# schema1.net
KiCad netlist of a schematic drawn in Altium Designer
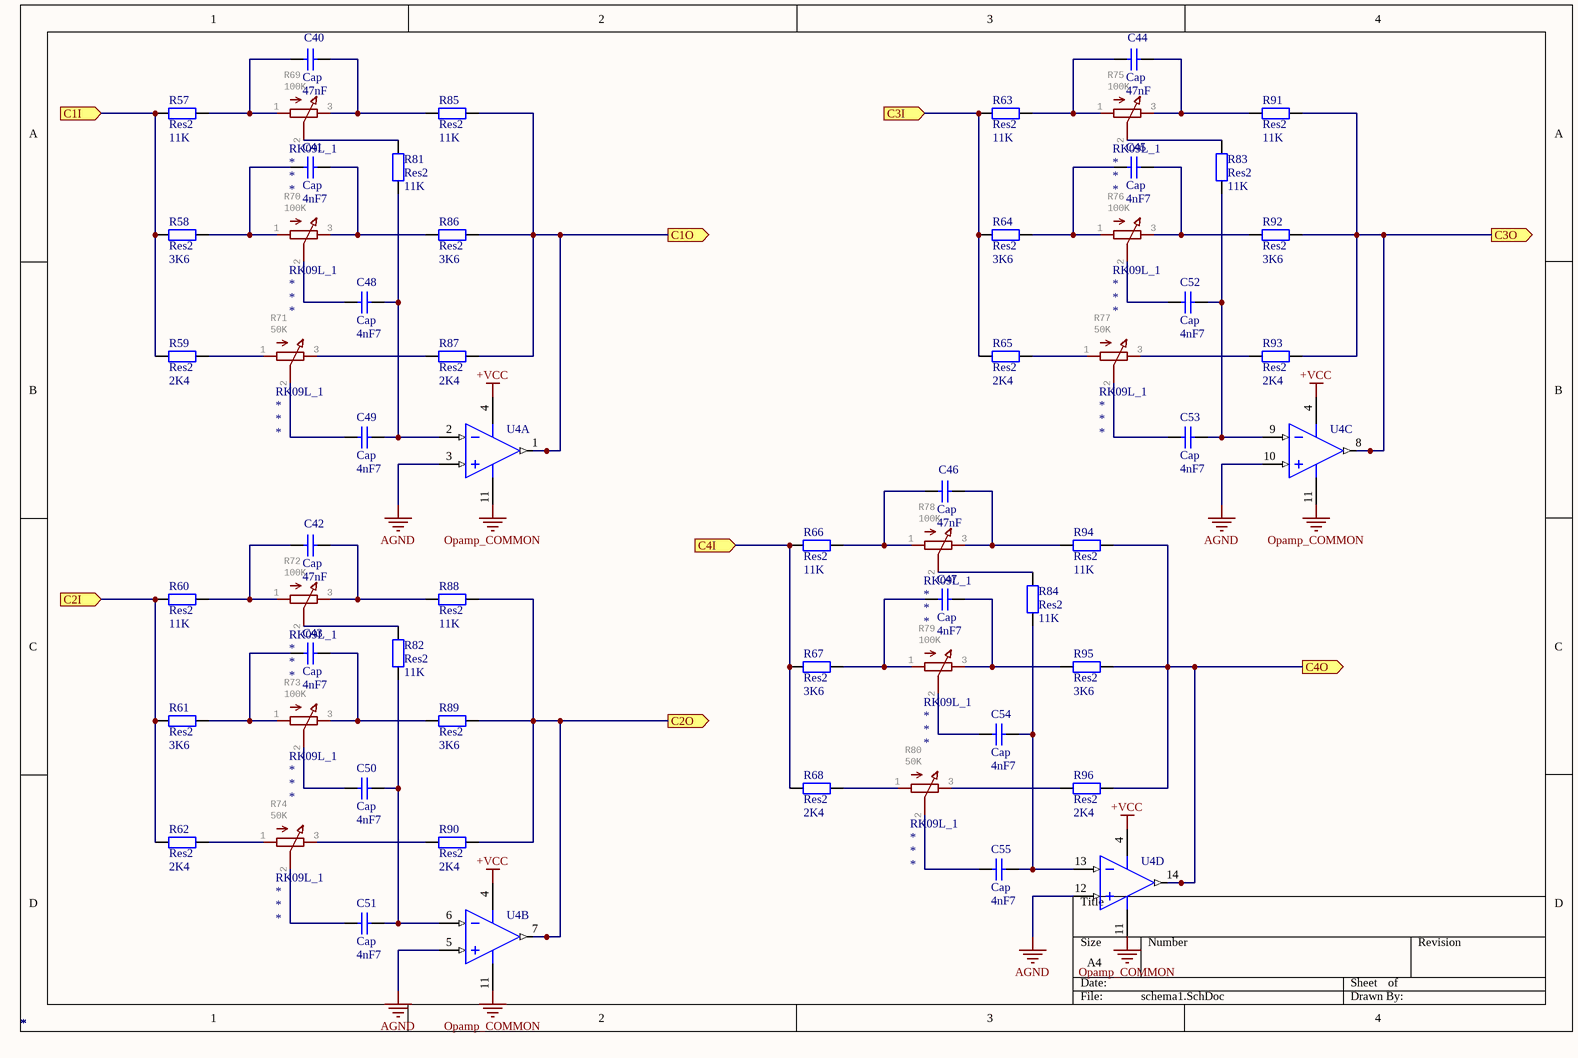
[diagram p0: schema1.SchDoc]

(export (version "E")
  (design (tool "Eeschema 10.0.6"))
  (components
    (comp (ref "C40")
      (value "Cap")
      (footprint "SMD_CAPACITOR")
      (description "Capacitor")
      (fields (field (name "ALTIUM_VALUE") "47nF") (field (name "PUBLISHER") "Altium Limited"))
      (libsource (lib "Miscellaneous Devices") (part "Cap"))
    )
    (comp (ref "C41")
      (value "Cap")
      (footprint "SMD_CAPACITOR")
      (description "Capacitor")
      (fields (field (name "ALTIUM_VALUE") "4nF7") (field (name "PUBLISHER") "Altium Limited"))
      (libsource (lib "Miscellaneous Devices") (part "Cap"))
    )
    (comp (ref "C42")
      (value "Cap")
      (footprint "SMD_CAPACITOR")
      (description "Capacitor")
      (fields (field (name "ALTIUM_VALUE") "47nF") (field (name "PUBLISHER") "Altium Limited"))
      (libsource (lib "Miscellaneous Devices") (part "Cap"))
    )
    (comp (ref "C43")
      (value "Cap")
      (footprint "SMD_CAPACITOR")
      (description "Capacitor")
      (fields (field (name "ALTIUM_VALUE") "4nF7") (field (name "PUBLISHER") "Altium Limited"))
      (libsource (lib "Miscellaneous Devices") (part "Cap"))
    )
    (comp (ref "C44")
      (value "Cap")
      (footprint "SMD_CAPACITOR")
      (description "Capacitor")
      (fields (field (name "ALTIUM_VALUE") "47nF") (field (name "PUBLISHER") "Altium Limited"))
      (libsource (lib "Miscellaneous Devices") (part "Cap"))
    )
    (comp (ref "C45")
      (value "Cap")
      (footprint "SMD_CAPACITOR")
      (description "Capacitor")
      (fields (field (name "ALTIUM_VALUE") "4nF7") (field (name "PUBLISHER") "Altium Limited"))
      (libsource (lib "Miscellaneous Devices") (part "Cap"))
    )
    (comp (ref "C46")
      (value "Cap")
      (footprint "SMD_CAPACITOR")
      (description "Capacitor")
      (fields (field (name "ALTIUM_VALUE") "47nF") (field (name "PUBLISHER") "Altium Limited"))
      (libsource (lib "Miscellaneous Devices") (part "Cap"))
    )
    (comp (ref "C47")
      (value "Cap")
      (footprint "SMD_CAPACITOR")
      (description "Capacitor")
      (fields (field (name "ALTIUM_VALUE") "4nF7") (field (name "PUBLISHER") "Altium Limited"))
      (libsource (lib "Miscellaneous Devices") (part "Cap"))
    )
    (comp (ref "C48")
      (value "Cap")
      (footprint "SMD_CAPACITOR")
      (description "Capacitor")
      (fields (field (name "ALTIUM_VALUE") "4nF7") (field (name "PUBLISHER") "Altium Limited"))
      (libsource (lib "Miscellaneous Devices") (part "Cap"))
    )
    (comp (ref "C49")
      (value "Cap")
      (footprint "SMD_CAPACITOR")
      (description "Capacitor")
      (fields (field (name "ALTIUM_VALUE") "4nF7") (field (name "PUBLISHER") "Altium Limited"))
      (libsource (lib "Miscellaneous Devices") (part "Cap"))
    )
    (comp (ref "C50")
      (value "Cap")
      (footprint "SMD_CAPACITOR")
      (description "Capacitor")
      (fields (field (name "ALTIUM_VALUE") "4nF7") (field (name "PUBLISHER") "Altium Limited"))
      (libsource (lib "Miscellaneous Devices") (part "Cap"))
    )
    (comp (ref "C51")
      (value "Cap")
      (footprint "SMD_CAPACITOR")
      (description "Capacitor")
      (fields (field (name "ALTIUM_VALUE") "4nF7") (field (name "PUBLISHER") "Altium Limited"))
      (libsource (lib "Miscellaneous Devices") (part "Cap"))
    )
    (comp (ref "C52")
      (value "Cap")
      (footprint "SMD_CAPACITOR")
      (description "Capacitor")
      (fields (field (name "ALTIUM_VALUE") "4nF7") (field (name "PUBLISHER") "Altium Limited"))
      (libsource (lib "Miscellaneous Devices") (part "Cap"))
    )
    (comp (ref "C53")
      (value "Cap")
      (footprint "SMD_CAPACITOR")
      (description "Capacitor")
      (fields (field (name "ALTIUM_VALUE") "4nF7") (field (name "PUBLISHER") "Altium Limited"))
      (libsource (lib "Miscellaneous Devices") (part "Cap"))
    )
    (comp (ref "C54")
      (value "Cap")
      (footprint "SMD_CAPACITOR")
      (description "Capacitor")
      (fields (field (name "ALTIUM_VALUE") "4nF7") (field (name "PUBLISHER") "Altium Limited"))
      (libsource (lib "Miscellaneous Devices") (part "Cap"))
    )
    (comp (ref "C55")
      (value "Cap")
      (footprint "SMD_CAPACITOR")
      (description "Capacitor")
      (fields (field (name "ALTIUM_VALUE") "4nF7") (field (name "PUBLISHER") "Altium Limited"))
      (libsource (lib "Miscellaneous Devices") (part "Cap"))
    )
    (comp (ref "R57")
      (value "Res2")
      (footprint "SMD_RESISTOR")
      (description "Resistor")
      (fields (field (name "ALTIUM_VALUE") "11K") (field (name "PUBLISHER") "Altium Limited"))
      (libsource (lib "Miscellaneous Devices") (part "Res2"))
    )
    (comp (ref "R58")
      (value "Res2")
      (footprint "SMD_RESISTOR")
      (description "Resistor")
      (fields (field (name "ALTIUM_VALUE") "3K6") (field (name "PUBLISHER") "Altium Limited"))
      (libsource (lib "Miscellaneous Devices") (part "Res2"))
    )
    (comp (ref "R59")
      (value "Res2")
      (footprint "SMD_RESISTOR")
      (description "Resistor")
      (fields (field (name "ALTIUM_VALUE") "2K4") (field (name "PUBLISHER") "Altium Limited"))
      (libsource (lib "Miscellaneous Devices") (part "Res2"))
    )
    (comp (ref "R60")
      (value "Res2")
      (footprint "SMD_RESISTOR")
      (description "Resistor")
      (fields (field (name "ALTIUM_VALUE") "11K") (field (name "PUBLISHER") "Altium Limited"))
      (libsource (lib "Miscellaneous Devices") (part "Res2"))
    )
    (comp (ref "R61")
      (value "Res2")
      (footprint "SMD_RESISTOR")
      (description "Resistor")
      (fields (field (name "ALTIUM_VALUE") "3K6") (field (name "PUBLISHER") "Altium Limited"))
      (libsource (lib "Miscellaneous Devices") (part "Res2"))
    )
    (comp (ref "R62")
      (value "Res2")
      (footprint "SMD_RESISTOR")
      (description "Resistor")
      (fields (field (name "ALTIUM_VALUE") "2K4") (field (name "PUBLISHER") "Altium Limited"))
      (libsource (lib "Miscellaneous Devices") (part "Res2"))
    )
    (comp (ref "R63")
      (value "Res2")
      (footprint "SMD_RESISTOR")
      (description "Resistor")
      (fields (field (name "ALTIUM_VALUE") "11K") (field (name "PUBLISHER") "Altium Limited"))
      (libsource (lib "Miscellaneous Devices") (part "Res2"))
    )
    (comp (ref "R64")
      (value "Res2")
      (footprint "SMD_RESISTOR")
      (description "Resistor")
      (fields (field (name "ALTIUM_VALUE") "3K6") (field (name "PUBLISHER") "Altium Limited"))
      (libsource (lib "Miscellaneous Devices") (part "Res2"))
    )
    (comp (ref "R65")
      (value "Res2")
      (footprint "SMD_RESISTOR")
      (description "Resistor")
      (fields (field (name "ALTIUM_VALUE") "2K4") (field (name "PUBLISHER") "Altium Limited"))
      (libsource (lib "Miscellaneous Devices") (part "Res2"))
    )
    (comp (ref "R66")
      (value "Res2")
      (footprint "SMD_RESISTOR")
      (description "Resistor")
      (fields (field (name "ALTIUM_VALUE") "11K") (field (name "PUBLISHER") "Altium Limited"))
      (libsource (lib "Miscellaneous Devices") (part "Res2"))
    )
    (comp (ref "R67")
      (value "Res2")
      (footprint "SMD_RESISTOR")
      (description "Resistor")
      (fields (field (name "ALTIUM_VALUE") "3K6") (field (name "PUBLISHER") "Altium Limited"))
      (libsource (lib "Miscellaneous Devices") (part "Res2"))
    )
    (comp (ref "R68")
      (value "Res2")
      (footprint "SMD_RESISTOR")
      (description "Resistor")
      (fields (field (name "ALTIUM_VALUE") "2K4") (field (name "PUBLISHER") "Altium Limited"))
      (libsource (lib "Miscellaneous Devices") (part "Res2"))
    )
    (comp (ref "R69")
      (value "100K")
      (footprint "RK09L1140A65")
      (fields
        (field (name "ALTIUM_UNNAMED_1") "*")
        (field (name "ALTIUM_UNNAMED_2") "*")
        (field (name "ALTIUM_UNNAMED_3") "*")
        (field (name "ALTIUM_UNNAMED_4") "RK09L_1")
        (field (name "ALTIUM_UNNAMED_5") "*")
        (field (name "ALTIUM_UNNAMED_6") "*")
        (field (name "ALTIUM_UNNAMED_7") "*")
        (field (name "ALTIUM_UNNAMED_8") "*")
        (field (name "ALTIUM_UNNAMED_9") "*")
        (field (name "LIBRARYNAME") "SD_Pots")
      )
      (libsource (lib "equalizer_project") (part "RK09L_1"))
    )
    (comp (ref "R70")
      (value "100K")
      (footprint "RK09L1140A65")
      (fields
        (field (name "ALTIUM_UNNAMED_1") "*")
        (field (name "ALTIUM_UNNAMED_2") "*")
        (field (name "ALTIUM_UNNAMED_3") "*")
        (field (name "ALTIUM_UNNAMED_4") "RK09L_1")
        (field (name "ALTIUM_UNNAMED_5") "*")
        (field (name "ALTIUM_UNNAMED_6") "*")
        (field (name "ALTIUM_UNNAMED_7") "*")
        (field (name "ALTIUM_UNNAMED_8") "*")
        (field (name "ALTIUM_UNNAMED_9") "*")
        (field (name "LIBRARYNAME") "SD_Pots")
      )
      (libsource (lib "equalizer_project") (part "RK09L_1"))
    )
    (comp (ref "R71")
      (value "50K")
      (footprint "RK09L1140A65")
      (fields
        (field (name "ALTIUM_UNNAMED_1") "*")
        (field (name "ALTIUM_UNNAMED_2") "*")
        (field (name "ALTIUM_UNNAMED_3") "*")
        (field (name "ALTIUM_UNNAMED_4") "RK09L_1")
        (field (name "ALTIUM_UNNAMED_5") "*")
        (field (name "ALTIUM_UNNAMED_6") "*")
        (field (name "ALTIUM_UNNAMED_7") "*")
        (field (name "ALTIUM_UNNAMED_8") "*")
        (field (name "ALTIUM_UNNAMED_9") "*")
        (field (name "LIBRARYNAME") "SD_Pots")
      )
      (libsource (lib "equalizer_project") (part "RK09L_1"))
    )
    (comp (ref "R72")
      (value "100K")
      (footprint "RK09L1140A65")
      (fields
        (field (name "ALTIUM_UNNAMED_1") "*")
        (field (name "ALTIUM_UNNAMED_2") "*")
        (field (name "ALTIUM_UNNAMED_3") "*")
        (field (name "ALTIUM_UNNAMED_4") "RK09L_1")
        (field (name "ALTIUM_UNNAMED_5") "*")
        (field (name "ALTIUM_UNNAMED_6") "*")
        (field (name "ALTIUM_UNNAMED_7") "*")
        (field (name "ALTIUM_UNNAMED_8") "*")
        (field (name "ALTIUM_UNNAMED_9") "*")
        (field (name "LIBRARYNAME") "SD_Pots")
      )
      (libsource (lib "equalizer_project") (part "RK09L_1"))
    )
    (comp (ref "R73")
      (value "100K")
      (footprint "RK09L1140A65")
      (fields
        (field (name "ALTIUM_UNNAMED_1") "*")
        (field (name "ALTIUM_UNNAMED_2") "*")
        (field (name "ALTIUM_UNNAMED_3") "*")
        (field (name "ALTIUM_UNNAMED_4") "RK09L_1")
        (field (name "ALTIUM_UNNAMED_5") "*")
        (field (name "ALTIUM_UNNAMED_6") "*")
        (field (name "ALTIUM_UNNAMED_7") "*")
        (field (name "ALTIUM_UNNAMED_8") "*")
        (field (name "ALTIUM_UNNAMED_9") "*")
        (field (name "LIBRARYNAME") "SD_Pots")
      )
      (libsource (lib "equalizer_project") (part "RK09L_1"))
    )
    (comp (ref "R74")
      (value "50K")
      (footprint "RK09L1140A65")
      (fields
        (field (name "ALTIUM_UNNAMED_1") "*")
        (field (name "ALTIUM_UNNAMED_2") "*")
        (field (name "ALTIUM_UNNAMED_3") "*")
        (field (name "ALTIUM_UNNAMED_4") "RK09L_1")
        (field (name "ALTIUM_UNNAMED_5") "*")
        (field (name "ALTIUM_UNNAMED_6") "*")
        (field (name "ALTIUM_UNNAMED_7") "*")
        (field (name "ALTIUM_UNNAMED_8") "*")
        (field (name "ALTIUM_UNNAMED_9") "*")
        (field (name "LIBRARYNAME") "SD_Pots")
      )
      (libsource (lib "equalizer_project") (part "RK09L_1"))
    )
    (comp (ref "R75")
      (value "100K")
      (footprint "RK09L1140A65")
      (fields
        (field (name "ALTIUM_UNNAMED_1") "*")
        (field (name "ALTIUM_UNNAMED_2") "*")
        (field (name "ALTIUM_UNNAMED_3") "*")
        (field (name "ALTIUM_UNNAMED_4") "RK09L_1")
        (field (name "ALTIUM_UNNAMED_5") "*")
        (field (name "ALTIUM_UNNAMED_6") "*")
        (field (name "ALTIUM_UNNAMED_7") "*")
        (field (name "ALTIUM_UNNAMED_8") "*")
        (field (name "ALTIUM_UNNAMED_9") "*")
        (field (name "LIBRARYNAME") "SD_Pots")
      )
      (libsource (lib "equalizer_project") (part "RK09L_1"))
    )
    (comp (ref "R76")
      (value "100K")
      (footprint "RK09L1140A65")
      (fields
        (field (name "ALTIUM_UNNAMED_1") "*")
        (field (name "ALTIUM_UNNAMED_2") "*")
        (field (name "ALTIUM_UNNAMED_3") "*")
        (field (name "ALTIUM_UNNAMED_4") "RK09L_1")
        (field (name "ALTIUM_UNNAMED_5") "*")
        (field (name "ALTIUM_UNNAMED_6") "*")
        (field (name "ALTIUM_UNNAMED_7") "*")
        (field (name "ALTIUM_UNNAMED_8") "*")
        (field (name "ALTIUM_UNNAMED_9") "*")
        (field (name "LIBRARYNAME") "SD_Pots")
      )
      (libsource (lib "equalizer_project") (part "RK09L_1"))
    )
    (comp (ref "R77")
      (value "50K")
      (footprint "RK09L1140A65")
      (fields
        (field (name "ALTIUM_UNNAMED_1") "*")
        (field (name "ALTIUM_UNNAMED_2") "*")
        (field (name "ALTIUM_UNNAMED_3") "*")
        (field (name "ALTIUM_UNNAMED_4") "RK09L_1")
        (field (name "ALTIUM_UNNAMED_5") "*")
        (field (name "ALTIUM_UNNAMED_6") "*")
        (field (name "ALTIUM_UNNAMED_7") "*")
        (field (name "ALTIUM_UNNAMED_8") "*")
        (field (name "ALTIUM_UNNAMED_9") "*")
        (field (name "LIBRARYNAME") "SD_Pots")
      )
      (libsource (lib "equalizer_project") (part "RK09L_1"))
    )
    (comp (ref "R78")
      (value "100K")
      (footprint "RK09L1140A65")
      (fields
        (field (name "ALTIUM_UNNAMED_1") "*")
        (field (name "ALTIUM_UNNAMED_2") "*")
        (field (name "ALTIUM_UNNAMED_3") "*")
        (field (name "ALTIUM_UNNAMED_4") "RK09L_1")
        (field (name "ALTIUM_UNNAMED_5") "*")
        (field (name "ALTIUM_UNNAMED_6") "*")
        (field (name "ALTIUM_UNNAMED_7") "*")
        (field (name "ALTIUM_UNNAMED_8") "*")
        (field (name "ALTIUM_UNNAMED_9") "*")
        (field (name "LIBRARYNAME") "SD_Pots")
      )
      (libsource (lib "equalizer_project") (part "RK09L_1"))
    )
    (comp (ref "R79")
      (value "100K")
      (footprint "RK09L1140A65")
      (fields
        (field (name "ALTIUM_UNNAMED_1") "*")
        (field (name "ALTIUM_UNNAMED_2") "*")
        (field (name "ALTIUM_UNNAMED_3") "*")
        (field (name "ALTIUM_UNNAMED_4") "RK09L_1")
        (field (name "ALTIUM_UNNAMED_5") "*")
        (field (name "ALTIUM_UNNAMED_6") "*")
        (field (name "ALTIUM_UNNAMED_7") "*")
        (field (name "ALTIUM_UNNAMED_8") "*")
        (field (name "ALTIUM_UNNAMED_9") "*")
        (field (name "LIBRARYNAME") "SD_Pots")
      )
      (libsource (lib "equalizer_project") (part "RK09L_1"))
    )
    (comp (ref "R80")
      (value "50K")
      (footprint "RK09L1140A65")
      (fields
        (field (name "ALTIUM_UNNAMED_1") "*")
        (field (name "ALTIUM_UNNAMED_2") "*")
        (field (name "ALTIUM_UNNAMED_3") "*")
        (field (name "ALTIUM_UNNAMED_4") "RK09L_1")
        (field (name "ALTIUM_UNNAMED_5") "*")
        (field (name "ALTIUM_UNNAMED_6") "*")
        (field (name "ALTIUM_UNNAMED_7") "*")
        (field (name "ALTIUM_UNNAMED_8") "*")
        (field (name "ALTIUM_UNNAMED_9") "*")
        (field (name "LIBRARYNAME") "SD_Pots")
      )
      (libsource (lib "equalizer_project") (part "RK09L_1"))
    )
    (comp (ref "R81")
      (value "Res2")
      (footprint "SMD_RESISTOR")
      (description "Resistor")
      (fields (field (name "ALTIUM_VALUE") "11K") (field (name "PUBLISHER") "Altium Limited"))
      (libsource (lib "") (part "Res2_1"))
    )
    (comp (ref "R82")
      (value "Res2")
      (footprint "SMD_RESISTOR")
      (description "Resistor")
      (fields (field (name "ALTIUM_VALUE") "11K") (field (name "PUBLISHER") "Altium Limited"))
      (libsource (lib "") (part "Res2_1"))
    )
    (comp (ref "R83")
      (value "Res2")
      (footprint "SMD_RESISTOR")
      (description "Resistor")
      (fields (field (name "ALTIUM_VALUE") "11K") (field (name "PUBLISHER") "Altium Limited"))
      (libsource (lib "") (part "Res2_1"))
    )
    (comp (ref "R84")
      (value "Res2")
      (footprint "SMD_RESISTOR")
      (description "Resistor")
      (fields (field (name "ALTIUM_VALUE") "11K") (field (name "PUBLISHER") "Altium Limited"))
      (libsource (lib "") (part "Res2_1"))
    )
    (comp (ref "R85")
      (value "Res2")
      (footprint "SMD_RESISTOR")
      (description "Resistor")
      (fields (field (name "ALTIUM_VALUE") "11K") (field (name "PUBLISHER") "Altium Limited"))
      (libsource (lib "Miscellaneous Devices") (part "Res2"))
    )
    (comp (ref "R86")
      (value "Res2")
      (footprint "SMD_RESISTOR")
      (description "Resistor")
      (fields (field (name "ALTIUM_VALUE") "3K6") (field (name "PUBLISHER") "Altium Limited"))
      (libsource (lib "Miscellaneous Devices") (part "Res2"))
    )
    (comp (ref "R87")
      (value "Res2")
      (footprint "SMD_RESISTOR")
      (description "Resistor")
      (fields (field (name "ALTIUM_VALUE") "2K4") (field (name "PUBLISHER") "Altium Limited"))
      (libsource (lib "Miscellaneous Devices") (part "Res2"))
    )
    (comp (ref "R88")
      (value "Res2")
      (footprint "SMD_RESISTOR")
      (description "Resistor")
      (fields (field (name "ALTIUM_VALUE") "11K") (field (name "PUBLISHER") "Altium Limited"))
      (libsource (lib "Miscellaneous Devices") (part "Res2"))
    )
    (comp (ref "R89")
      (value "Res2")
      (footprint "SMD_RESISTOR")
      (description "Resistor")
      (fields (field (name "ALTIUM_VALUE") "3K6") (field (name "PUBLISHER") "Altium Limited"))
      (libsource (lib "Miscellaneous Devices") (part "Res2"))
    )
    (comp (ref "R90")
      (value "Res2")
      (footprint "SMD_RESISTOR")
      (description "Resistor")
      (fields (field (name "ALTIUM_VALUE") "2K4") (field (name "PUBLISHER") "Altium Limited"))
      (libsource (lib "Miscellaneous Devices") (part "Res2"))
    )
    (comp (ref "R91")
      (value "Res2")
      (footprint "SMD_RESISTOR")
      (description "Resistor")
      (fields (field (name "ALTIUM_VALUE") "11K") (field (name "PUBLISHER") "Altium Limited"))
      (libsource (lib "Miscellaneous Devices") (part "Res2"))
    )
    (comp (ref "R92")
      (value "Res2")
      (footprint "SMD_RESISTOR")
      (description "Resistor")
      (fields (field (name "ALTIUM_VALUE") "3K6") (field (name "PUBLISHER") "Altium Limited"))
      (libsource (lib "Miscellaneous Devices") (part "Res2"))
    )
    (comp (ref "R93")
      (value "Res2")
      (footprint "SMD_RESISTOR")
      (description "Resistor")
      (fields (field (name "ALTIUM_VALUE") "2K4") (field (name "PUBLISHER") "Altium Limited"))
      (libsource (lib "Miscellaneous Devices") (part "Res2"))
    )
    (comp (ref "R94")
      (value "Res2")
      (footprint "SMD_RESISTOR")
      (description "Resistor")
      (fields (field (name "ALTIUM_VALUE") "11K") (field (name "PUBLISHER") "Altium Limited"))
      (libsource (lib "Miscellaneous Devices") (part "Res2"))
    )
    (comp (ref "R95")
      (value "Res2")
      (footprint "SMD_RESISTOR")
      (description "Resistor")
      (fields (field (name "ALTIUM_VALUE") "3K6") (field (name "PUBLISHER") "Altium Limited"))
      (libsource (lib "Miscellaneous Devices") (part "Res2"))
    )
    (comp (ref "R96")
      (value "Res2")
      (footprint "SMD_RESISTOR")
      (description "Resistor")
      (fields (field (name "ALTIUM_VALUE") "2K4") (field (name "PUBLISHER") "Altium Limited"))
      (libsource (lib "Miscellaneous Devices") (part "Res2"))
    )
    (comp (ref "U4")
      (value "OPA1664AIDR")
      (footprint "OPA1664AIDR")
      (fields (field (name "MANUFACTURER") "Texas Instruments"))
      (libsource (lib "equalizer_project") (part "CMP-0272-00211-3"))
    )
  )
  (nets
    (net (code "1") (name "+VCC") (class "Default")
      (node (ref "U4") (pin "4") (pinfunction "V+_4") (pintype "power_in"))
    )
    (net (code "2") (name "/C1I") (class "Default")
      (node (ref "R57") (pin "1") (pinfunction "1_1") (pintype "passive"))
      (node (ref "R58") (pin "1") (pinfunction "1_1") (pintype "passive"))
      (node (ref "R59") (pin "1") (pinfunction "1_1") (pintype "passive"))
    )
    (net (code "3") (name "/C1O") (class "Default")
      (node (ref "R85") (pin "2") (pinfunction "2_2") (pintype "passive"))
      (node (ref "R86") (pin "2") (pinfunction "2_2") (pintype "passive"))
      (node (ref "R87") (pin "2") (pinfunction "2_2") (pintype "passive"))
      (node (ref "U4") (pin "1") (pinfunction "OUT_A_1") (pintype "output"))
    )
    (net (code "4") (name "/C2I") (class "Default")
      (node (ref "R60") (pin "1") (pinfunction "1_1") (pintype "passive"))
      (node (ref "R61") (pin "1") (pinfunction "1_1") (pintype "passive"))
      (node (ref "R62") (pin "1") (pinfunction "1_1") (pintype "passive"))
    )
    (net (code "5") (name "/C2O") (class "Default")
      (node (ref "R88") (pin "2") (pinfunction "2_2") (pintype "passive"))
      (node (ref "R89") (pin "2") (pinfunction "2_2") (pintype "passive"))
      (node (ref "R90") (pin "2") (pinfunction "2_2") (pintype "passive"))
      (node (ref "U4") (pin "7") (pinfunction "OUT_B_7") (pintype "output"))
    )
    (net (code "6") (name "/C3I") (class "Default")
      (node (ref "R63") (pin "1") (pinfunction "1_1") (pintype "passive"))
      (node (ref "R64") (pin "1") (pinfunction "1_1") (pintype "passive"))
      (node (ref "R65") (pin "1") (pinfunction "1_1") (pintype "passive"))
    )
    (net (code "7") (name "/C3O") (class "Default")
      (node (ref "R91") (pin "2") (pinfunction "2_2") (pintype "passive"))
      (node (ref "R92") (pin "2") (pinfunction "2_2") (pintype "passive"))
      (node (ref "R93") (pin "2") (pinfunction "2_2") (pintype "passive"))
      (node (ref "U4") (pin "8") (pinfunction "OUT_C_8") (pintype "output"))
    )
    (net (code "8") (name "/C4I") (class "Default")
      (node (ref "R66") (pin "1") (pinfunction "1_1") (pintype "passive"))
      (node (ref "R67") (pin "1") (pinfunction "1_1") (pintype "passive"))
      (node (ref "R68") (pin "1") (pinfunction "1_1") (pintype "passive"))
    )
    (net (code "9") (name "/C4O") (class "Default")
      (node (ref "R94") (pin "2") (pinfunction "2_2") (pintype "passive"))
      (node (ref "R95") (pin "2") (pinfunction "2_2") (pintype "passive"))
      (node (ref "R96") (pin "2") (pinfunction "2_2") (pintype "passive"))
      (node (ref "U4") (pin "14") (pinfunction "OUT_D_14") (pintype "output"))
    )
    (net (code "10") (name "AGND") (class "Default")
      (node (ref "U4") (pin "10") (pinfunction "IN_C+_10") (pintype "input"))
      (node (ref "U4") (pin "12") (pinfunction "IN_D+_12") (pintype "input"))
      (node (ref "U4") (pin "3") (pinfunction "IN_A+_3") (pintype "input"))
      (node (ref "U4") (pin "5") (pinfunction "IN_B+_5") (pintype "input"))
    )
    (net (code "11") (name "Net-(C40-Pad1)") (class "Default")
      (node (ref "C40") (pin "1") (pinfunction "1_1") (pintype "passive"))
      (node (ref "R57") (pin "2") (pinfunction "2_2") (pintype "passive"))
      (node (ref "R69") (pin "1") (pinfunction "1_1") (pintype "passive"))
    )
    (net (code "12") (name "Net-(C40-Pad2)") (class "Default")
      (node (ref "C40") (pin "2") (pinfunction "2_2") (pintype "passive"))
      (node (ref "R69") (pin "3") (pinfunction "3_3") (pintype "passive"))
      (node (ref "R85") (pin "1") (pinfunction "1_1") (pintype "passive"))
    )
    (net (code "13") (name "Net-(C41-Pad1)") (class "Default")
      (node (ref "C41") (pin "1") (pinfunction "1_1") (pintype "passive"))
      (node (ref "R58") (pin "2") (pinfunction "2_2") (pintype "passive"))
      (node (ref "R70") (pin "1") (pinfunction "1_1") (pintype "passive"))
    )
    (net (code "14") (name "Net-(C41-Pad2)") (class "Default")
      (node (ref "C41") (pin "2") (pinfunction "2_2") (pintype "passive"))
      (node (ref "R70") (pin "3") (pinfunction "3_3") (pintype "passive"))
      (node (ref "R86") (pin "1") (pinfunction "1_1") (pintype "passive"))
    )
    (net (code "15") (name "Net-(C42-Pad1)") (class "Default")
      (node (ref "C42") (pin "1") (pinfunction "1_1") (pintype "passive"))
      (node (ref "R60") (pin "2") (pinfunction "2_2") (pintype "passive"))
      (node (ref "R72") (pin "1") (pinfunction "1_1") (pintype "passive"))
    )
    (net (code "16") (name "Net-(C42-Pad2)") (class "Default")
      (node (ref "C42") (pin "2") (pinfunction "2_2") (pintype "passive"))
      (node (ref "R72") (pin "3") (pinfunction "3_3") (pintype "passive"))
      (node (ref "R88") (pin "1") (pinfunction "1_1") (pintype "passive"))
    )
    (net (code "17") (name "Net-(C43-Pad1)") (class "Default")
      (node (ref "C43") (pin "1") (pinfunction "1_1") (pintype "passive"))
      (node (ref "R61") (pin "2") (pinfunction "2_2") (pintype "passive"))
      (node (ref "R73") (pin "1") (pinfunction "1_1") (pintype "passive"))
    )
    (net (code "18") (name "Net-(C43-Pad2)") (class "Default")
      (node (ref "C43") (pin "2") (pinfunction "2_2") (pintype "passive"))
      (node (ref "R73") (pin "3") (pinfunction "3_3") (pintype "passive"))
      (node (ref "R89") (pin "1") (pinfunction "1_1") (pintype "passive"))
    )
    (net (code "19") (name "Net-(C44-Pad1)") (class "Default")
      (node (ref "C44") (pin "1") (pinfunction "1_1") (pintype "passive"))
      (node (ref "R63") (pin "2") (pinfunction "2_2") (pintype "passive"))
      (node (ref "R75") (pin "1") (pinfunction "1_1") (pintype "passive"))
    )
    (net (code "20") (name "Net-(C44-Pad2)") (class "Default")
      (node (ref "C44") (pin "2") (pinfunction "2_2") (pintype "passive"))
      (node (ref "R75") (pin "3") (pinfunction "3_3") (pintype "passive"))
      (node (ref "R91") (pin "1") (pinfunction "1_1") (pintype "passive"))
    )
    (net (code "21") (name "Net-(C45-Pad1)") (class "Default")
      (node (ref "C45") (pin "1") (pinfunction "1_1") (pintype "passive"))
      (node (ref "R64") (pin "2") (pinfunction "2_2") (pintype "passive"))
      (node (ref "R76") (pin "1") (pinfunction "1_1") (pintype "passive"))
    )
    (net (code "22") (name "Net-(C45-Pad2)") (class "Default")
      (node (ref "C45") (pin "2") (pinfunction "2_2") (pintype "passive"))
      (node (ref "R76") (pin "3") (pinfunction "3_3") (pintype "passive"))
      (node (ref "R92") (pin "1") (pinfunction "1_1") (pintype "passive"))
    )
    (net (code "23") (name "Net-(C46-Pad1)") (class "Default")
      (node (ref "C46") (pin "1") (pinfunction "1_1") (pintype "passive"))
      (node (ref "R66") (pin "2") (pinfunction "2_2") (pintype "passive"))
      (node (ref "R78") (pin "1") (pinfunction "1_1") (pintype "passive"))
    )
    (net (code "24") (name "Net-(C46-Pad2)") (class "Default")
      (node (ref "C46") (pin "2") (pinfunction "2_2") (pintype "passive"))
      (node (ref "R78") (pin "3") (pinfunction "3_3") (pintype "passive"))
      (node (ref "R94") (pin "1") (pinfunction "1_1") (pintype "passive"))
    )
    (net (code "25") (name "Net-(C47-Pad1)") (class "Default")
      (node (ref "C47") (pin "1") (pinfunction "1_1") (pintype "passive"))
      (node (ref "R67") (pin "2") (pinfunction "2_2") (pintype "passive"))
      (node (ref "R79") (pin "1") (pinfunction "1_1") (pintype "passive"))
    )
    (net (code "26") (name "Net-(C47-Pad2)") (class "Default")
      (node (ref "C47") (pin "2") (pinfunction "2_2") (pintype "passive"))
      (node (ref "R79") (pin "3") (pinfunction "3_3") (pintype "passive"))
      (node (ref "R95") (pin "1") (pinfunction "1_1") (pintype "passive"))
    )
    (net (code "27") (name "Net-(C48-Pad1)") (class "Default")
      (node (ref "C48") (pin "1") (pinfunction "1_1") (pintype "passive"))
      (node (ref "R70") (pin "2") (pinfunction "2_2") (pintype "passive"))
    )
    (net (code "28") (name "Net-(C49-Pad1)") (class "Default")
      (node (ref "C49") (pin "1") (pinfunction "1_1") (pintype "passive"))
      (node (ref "R71") (pin "2") (pinfunction "2_2") (pintype "passive"))
    )
    (net (code "29") (name "Net-(C50-Pad1)") (class "Default")
      (node (ref "C50") (pin "1") (pinfunction "1_1") (pintype "passive"))
      (node (ref "R73") (pin "2") (pinfunction "2_2") (pintype "passive"))
    )
    (net (code "30") (name "Net-(C51-Pad1)") (class "Default")
      (node (ref "C51") (pin "1") (pinfunction "1_1") (pintype "passive"))
      (node (ref "R74") (pin "2") (pinfunction "2_2") (pintype "passive"))
    )
    (net (code "31") (name "Net-(C52-Pad1)") (class "Default")
      (node (ref "C52") (pin "1") (pinfunction "1_1") (pintype "passive"))
      (node (ref "R76") (pin "2") (pinfunction "2_2") (pintype "passive"))
    )
    (net (code "32") (name "Net-(C53-Pad1)") (class "Default")
      (node (ref "C53") (pin "1") (pinfunction "1_1") (pintype "passive"))
      (node (ref "R77") (pin "2") (pinfunction "2_2") (pintype "passive"))
    )
    (net (code "33") (name "Net-(C54-Pad1)") (class "Default")
      (node (ref "C54") (pin "1") (pinfunction "1_1") (pintype "passive"))
      (node (ref "R79") (pin "2") (pinfunction "2_2") (pintype "passive"))
    )
    (net (code "34") (name "Net-(C55-Pad1)") (class "Default")
      (node (ref "C55") (pin "1") (pinfunction "1_1") (pintype "passive"))
      (node (ref "R80") (pin "2") (pinfunction "2_2") (pintype "passive"))
    )
    (net (code "35") (name "Net-(R59-Pad2)") (class "Default")
      (node (ref "R59") (pin "2") (pinfunction "2_2") (pintype "passive"))
      (node (ref "R71") (pin "1") (pinfunction "1_1") (pintype "passive"))
    )
    (net (code "36") (name "Net-(R62-Pad2)") (class "Default")
      (node (ref "R62") (pin "2") (pinfunction "2_2") (pintype "passive"))
      (node (ref "R74") (pin "1") (pinfunction "1_1") (pintype "passive"))
    )
    (net (code "37") (name "Net-(R65-Pad2)") (class "Default")
      (node (ref "R65") (pin "2") (pinfunction "2_2") (pintype "passive"))
      (node (ref "R77") (pin "1") (pinfunction "1_1") (pintype "passive"))
    )
    (net (code "38") (name "Net-(R68-Pad2)") (class "Default")
      (node (ref "R68") (pin "2") (pinfunction "2_2") (pintype "passive"))
      (node (ref "R80") (pin "1") (pinfunction "1_1") (pintype "passive"))
    )
    (net (code "39") (name "Net-(R69-Pad2)") (class "Default")
      (node (ref "R69") (pin "2") (pinfunction "2_2") (pintype "passive"))
      (node (ref "R81") (pin "2") (pinfunction "2_2") (pintype "passive"))
    )
    (net (code "40") (name "Net-(R71-Pad3)") (class "Default")
      (node (ref "R71") (pin "3") (pinfunction "3_3") (pintype "passive"))
      (node (ref "R87") (pin "1") (pinfunction "1_1") (pintype "passive"))
    )
    (net (code "41") (name "Net-(R72-Pad2)") (class "Default")
      (node (ref "R72") (pin "2") (pinfunction "2_2") (pintype "passive"))
      (node (ref "R82") (pin "2") (pinfunction "2_2") (pintype "passive"))
    )
    (net (code "42") (name "Net-(R74-Pad3)") (class "Default")
      (node (ref "R74") (pin "3") (pinfunction "3_3") (pintype "passive"))
      (node (ref "R90") (pin "1") (pinfunction "1_1") (pintype "passive"))
    )
    (net (code "43") (name "Net-(R75-Pad2)") (class "Default")
      (node (ref "R75") (pin "2") (pinfunction "2_2") (pintype "passive"))
      (node (ref "R83") (pin "2") (pinfunction "2_2") (pintype "passive"))
    )
    (net (code "44") (name "Net-(R77-Pad3)") (class "Default")
      (node (ref "R77") (pin "3") (pinfunction "3_3") (pintype "passive"))
      (node (ref "R93") (pin "1") (pinfunction "1_1") (pintype "passive"))
    )
    (net (code "45") (name "Net-(R78-Pad2)") (class "Default")
      (node (ref "R78") (pin "2") (pinfunction "2_2") (pintype "passive"))
      (node (ref "R84") (pin "2") (pinfunction "2_2") (pintype "passive"))
    )
    (net (code "46") (name "Net-(R80-Pad3)") (class "Default")
      (node (ref "R80") (pin "3") (pinfunction "3_3") (pintype "passive"))
      (node (ref "R96") (pin "1") (pinfunction "1_1") (pintype "passive"))
    )
    (net (code "47") (name "Net-(U4A-IN_A-)") (class "Default")
      (node (ref "C48") (pin "2") (pinfunction "2_2") (pintype "passive"))
      (node (ref "C49") (pin "2") (pinfunction "2_2") (pintype "passive"))
      (node (ref "R81") (pin "1") (pinfunction "1_1") (pintype "passive"))
      (node (ref "U4") (pin "2") (pinfunction "IN_A-_2") (pintype "input"))
    )
    (net (code "48") (name "Net-(U4B-IN_B-)") (class "Default")
      (node (ref "C50") (pin "2") (pinfunction "2_2") (pintype "passive"))
      (node (ref "C51") (pin "2") (pinfunction "2_2") (pintype "passive"))
      (node (ref "R82") (pin "1") (pinfunction "1_1") (pintype "passive"))
      (node (ref "U4") (pin "6") (pinfunction "IN_B-_6") (pintype "input"))
    )
    (net (code "49") (name "Net-(U4C-IN_C-)") (class "Default")
      (node (ref "C52") (pin "2") (pinfunction "2_2") (pintype "passive"))
      (node (ref "C53") (pin "2") (pinfunction "2_2") (pintype "passive"))
      (node (ref "R83") (pin "1") (pinfunction "1_1") (pintype "passive"))
      (node (ref "U4") (pin "9") (pinfunction "IN_C-_9") (pintype "input"))
    )
    (net (code "50") (name "Net-(U4D-IN_D-)") (class "Default")
      (node (ref "C54") (pin "2") (pinfunction "2_2") (pintype "passive"))
      (node (ref "C55") (pin "2") (pinfunction "2_2") (pintype "passive"))
      (node (ref "R84") (pin "1") (pinfunction "1_1") (pintype "passive"))
      (node (ref "U4") (pin "13") (pinfunction "IN_D-_13") (pintype "input"))
    )
    (net (code "51") (name "Opamp_COMMON") (class "Default")
      (node (ref "U4") (pin "11") (pinfunction "V-_11") (pintype "power_in"))
    )
  )
)
